# inter.net
KiCad netlist of a schematic drawn in Altium Designer
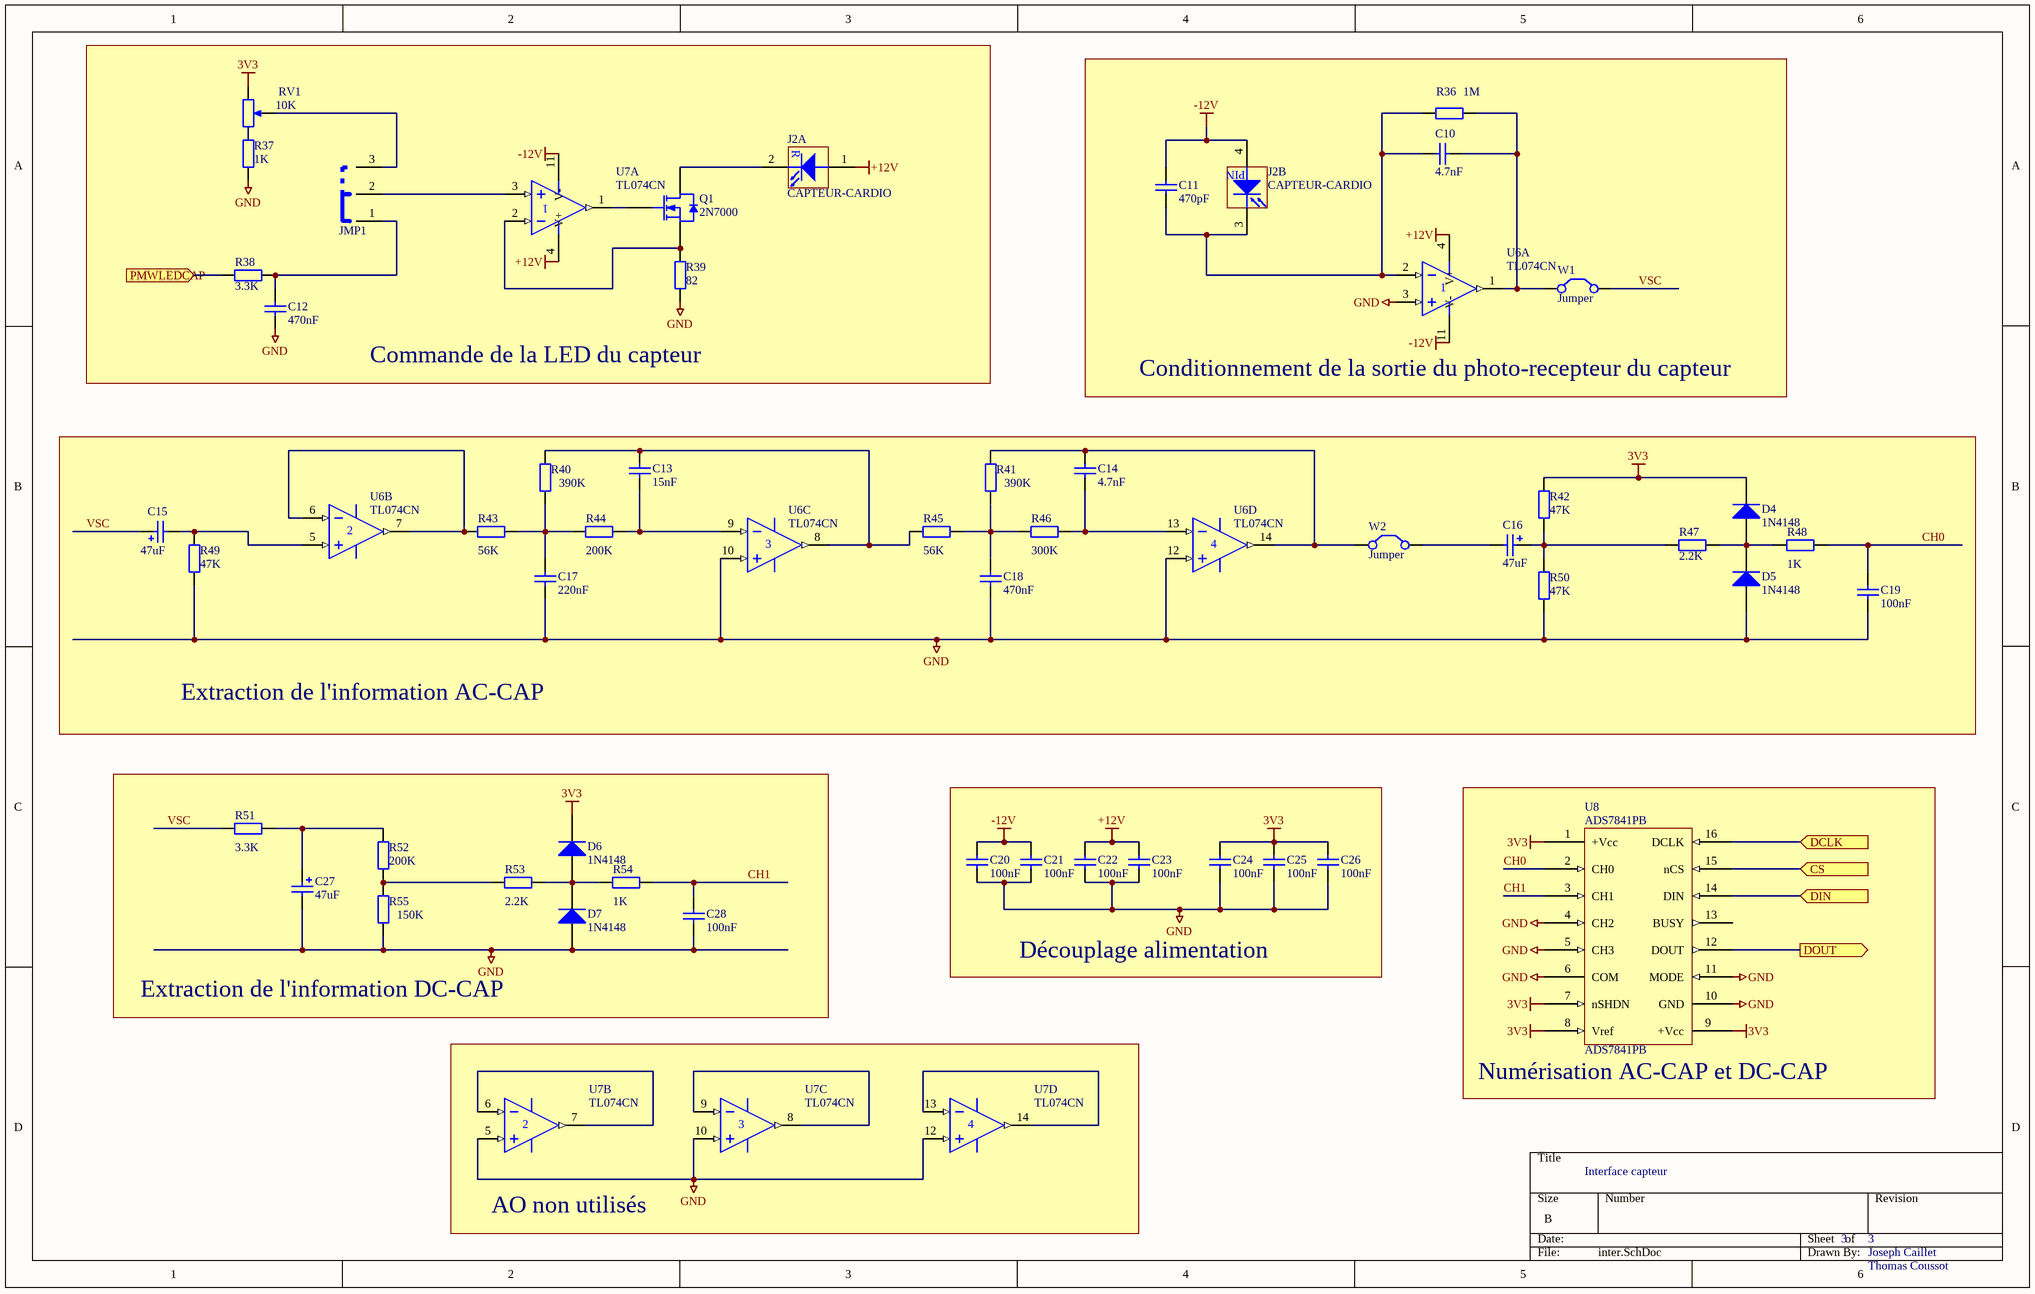
[diagram p0: inter.SchDoc]

(export (version "E")
  (design (tool "Eeschema 10.0.6"))
  (components
    (comp (ref "C10")
      (value "4.7nF")
      (footprint "rad-0.2-bot")
      (description "Capacitor Polyester 5%")
      (fields (field (name "PUBLISHER") "Altium Limited"))
      (libsource (lib "Miscellaneous Devices") (part "Cap"))
    )
    (comp (ref "C11")
      (value "470pF")
      (footprint "rad-0.2-bot")
      (description "Capacitor Polyester 5%")
      (fields (field (name "PUBLISHER") "Altium Limited"))
      (libsource (lib "Miscellaneous Devices") (part "Cap"))
    )
    (comp (ref "C12")
      (value "470nF")
      (footprint "rad-0.2-bot")
      (description "Capacitor Polyester 5%")
      (fields (field (name "PUBLISHER") "Altium Limited"))
      (libsource (lib "Miscellaneous Devices") (part "Cap"))
    )
    (comp (ref "C13")
      (value "15nF")
      (footprint "rad-0.2-bot")
      (description "Capacitor Polyester 5%")
      (fields (field (name "PUBLISHER") "Altium Limited"))
      (libsource (lib "Miscellaneous Devices") (part "Cap"))
    )
    (comp (ref "C14")
      (value "4.7nF")
      (footprint "rad-0.2-bot")
      (description "Capacitor Polyester 5%")
      (fields (field (name "PUBLISHER") "Altium Limited"))
      (libsource (lib "Miscellaneous Devices") (part "Cap"))
    )
    (comp (ref "C15")
      (value "47uF")
      (footprint "RAD-0.2-BOT")
      (description "Polarized Capacitor (Axial)")
      (fields (field (name "PUBLISHER") "Altium Limited"))
      (libsource (lib "Miscellaneous Devices") (part "Cap Pol1"))
    )
    (comp (ref "C16")
      (value "47uF")
      (footprint "RAD-0.2-BOT")
      (description "Polarized Capacitor (Axial)")
      (fields (field (name "PUBLISHER") "Altium Limited"))
      (libsource (lib "Miscellaneous Devices") (part "Cap Pol1"))
    )
    (comp (ref "C17")
      (value "220nF")
      (footprint "rad-0.2-bot")
      (description "Capacitor Polyester 5%")
      (fields (field (name "PUBLISHER") "Altium Limited"))
      (libsource (lib "Miscellaneous Devices") (part "Cap"))
    )
    (comp (ref "C18")
      (value "470nF")
      (footprint "rad-0.2-bot")
      (description "Capacitor Polyester 5%")
      (fields (field (name "PUBLISHER") "Altium Limited"))
      (libsource (lib "Miscellaneous Devices") (part "Cap"))
    )
    (comp (ref "C19")
      (value "100nF")
      (footprint "rad-0.2")
      (description "Capacitor Céramique Multicouche X7R 50V RadialPas=5.08mm 50%")
      (fields (field (name "PUBLISHER") "Altium Limited"))
      (libsource (lib "Miscellaneous Devices") (part "Cap"))
    )
    (comp (ref "C20")
      (value "100nF")
      (footprint "rad-0.2")
      (description "Capacitor Céramique Multicouche X7R 50V RadialPas=5.08mm 50%")
      (fields (field (name "PUBLISHER") "Altium Limited"))
      (libsource (lib "Miscellaneous Devices") (part "Cap"))
    )
    (comp (ref "C21")
      (value "100nF")
      (footprint "rad-0.2")
      (description "Capacitor Céramique Multicouche X7R 50V RadialPas=5.08mm 50%")
      (fields (field (name "PUBLISHER") "Altium Limited"))
      (libsource (lib "Miscellaneous Devices") (part "Cap"))
    )
    (comp (ref "C22")
      (value "100nF")
      (footprint "rad-0.2")
      (description "Capacitor Céramique Multicouche X7R 50V RadialPas=5.08mm 50%")
      (fields (field (name "PUBLISHER") "Altium Limited"))
      (libsource (lib "Miscellaneous Devices") (part "Cap"))
    )
    (comp (ref "C23")
      (value "100nF")
      (footprint "rad-0.2")
      (description "Capacitor Céramique Multicouche X7R 50V RadialPas=5.08mm 50%")
      (fields (field (name "PUBLISHER") "Altium Limited"))
      (libsource (lib "Miscellaneous Devices") (part "Cap"))
    )
    (comp (ref "C24")
      (value "100nF")
      (footprint "rad-0.2")
      (description "Capacitor Céramique Multicouche X7R 50V RadialPas=5.08mm 50%")
      (fields (field (name "PUBLISHER") "Altium Limited"))
      (libsource (lib "Miscellaneous Devices") (part "Cap"))
    )
    (comp (ref "C25")
      (value "100nF")
      (footprint "rad-0.2")
      (description "Capacitor Céramique Multicouche X7R 50V RadialPas=5.08mm 50%")
      (fields (field (name "PUBLISHER") "Altium Limited"))
      (libsource (lib "Miscellaneous Devices") (part "Cap"))
    )
    (comp (ref "C26")
      (value "100nF")
      (footprint "rad-0.2")
      (description "Capacitor Céramique Multicouche X7R 50V RadialPas=5.08mm 50%")
      (fields (field (name "PUBLISHER") "Altium Limited"))
      (libsource (lib "Miscellaneous Devices") (part "Cap"))
    )
    (comp (ref "C27")
      (value "47uF")
      (footprint "RAD-0.2-BOT")
      (description "Polarized Capacitor (Axial)")
      (fields (field (name "PUBLISHER") "Altium Limited"))
      (libsource (lib "Miscellaneous Devices") (part "Cap Pol1"))
    )
    (comp (ref "C28")
      (value "100nF")
      (footprint "rad-0.2")
      (description "Capacitor Céramique Multicouche X7R 50V RadialPas=5.08mm 50%")
      (fields (field (name "PUBLISHER") "Altium Limited"))
      (libsource (lib "Miscellaneous Devices") (part "Cap"))
    )
    (comp (ref "D4")
      (value "1N4148")
      (footprint "diode-0.4")
      (description "High Conductance Fast Diode")
      (fields (field (name "PUBLISHER") "Altium Limited"))
      (libsource (lib "FSC Discrete Diode") (part "1N4148"))
    )
    (comp (ref "D5")
      (value "1N4148")
      (footprint "diode-0.4")
      (description "High Conductance Fast Diode")
      (fields (field (name "PUBLISHER") "Altium Limited"))
      (libsource (lib "FSC Discrete Diode") (part "1N4148"))
    )
    (comp (ref "D6")
      (value "1N4148")
      (footprint "diode-0.4")
      (description "High Conductance Fast Diode")
      (fields (field (name "PUBLISHER") "Altium Limited"))
      (libsource (lib "FSC Discrete Diode") (part "1N4148"))
    )
    (comp (ref "D7")
      (value "1N4148")
      (footprint "diode-0.4")
      (description "High Conductance Fast Diode")
      (fields (field (name "PUBLISHER") "Altium Limited"))
      (libsource (lib "FSC Discrete Diode") (part "1N4148"))
    )
    (comp (ref "J2")
      (value "CAPTEUR-CARDIO")
      (footprint "KK-1X4M")
      (description "CAPTEUR CARDIO")
      (libsource (lib "schema_base_2016") (part "CAPTEUR-CARDIO"))
    )
    (comp (ref "JMP1")
      (value "JUMPER-INV")
      (footprint "JMP3-INV-0.1")
      (description "JUMPER INVERSEUR HE14 MALE 3 cts")
      (libsource (lib "schema_base_2016") (part "JUMPER-INV"))
    )
    (comp (ref "Q1")
      (value "2N7000")
      (footprint "NMOS-TO92")
      (description "N-channel Enhancement Mode Field-effect Transistor")
      (fields (field (name "PUBLISHER") "Altium Limited"))
      (libsource (lib "Philips Discrete MOSFET - Low Power") (part "2N7000"))
    )
    (comp (ref "R36")
      (value "1M")
      (footprint "axial-0.4")
      (description "Resistor 1% Couche métallique 0.4W Axial L=7mm")
      (fields (field (name "PUBLISHER") "Altium Limited"))
      (libsource (lib "") (part "Res2_3"))
    )
    (comp (ref "R37")
      (value "1K")
      (footprint "axial-0.4")
      (description "Resistor 5% Couche métallique 0.4W Axial L=7mm")
      (fields (field (name "PUBLISHER") "Altium Limited"))
      (libsource (lib "") (part "Res2_1"))
    )
    (comp (ref "R38")
      (value "3.3K")
      (footprint "axial-0.4")
      (description "Resistor 5% Couche métallique 0.4W Axial L=7mm")
      (fields (field (name "PUBLISHER") "Altium Limited"))
      (libsource (lib "") (part "Res2_3"))
    )
    (comp (ref "R39")
      (value "82")
      (footprint "axial-0.4")
      (description "Resistor 5% Couche métallique 0.4W Axial L=7mm")
      (fields (field (name "PUBLISHER") "Altium Limited"))
      (libsource (lib "") (part "Res2_2"))
    )
    (comp (ref "R40")
      (value "390K")
      (footprint "axial-0.4")
      (description "Resistor 1% Couche métallique 0.4W Axial L=7mm")
      (fields (field (name "PUBLISHER") "Altium Limited"))
      (libsource (lib "") (part "Res2_1"))
    )
    (comp (ref "R41")
      (value "390K")
      (footprint "axial-0.4")
      (description "Resistor 1% Couche métallique 0.4W Axial L=7mm")
      (fields (field (name "PUBLISHER") "Altium Limited"))
      (libsource (lib "") (part "Res2_1"))
    )
    (comp (ref "R42")
      (value "47K")
      (footprint "axial-0.4")
      (description "Resistor 1% Couche métallique 0.4W Axial L=7mm")
      (fields (field (name "PUBLISHER") "Altium Limited"))
      (libsource (lib "") (part "Res2_1"))
    )
    (comp (ref "R43")
      (value "56K")
      (footprint "axial-0.4")
      (description "Resistor 1% Couche métallique 0.4W Axial L=7mm")
      (fields (field (name "PUBLISHER") "Altium Limited"))
      (libsource (lib "Miscellaneous Devices") (part "Res2"))
    )
    (comp (ref "R44")
      (value "200K")
      (footprint "axial-0.4")
      (description "Resistor 1% Couche métallique 0.4W Axial L=7mm")
      (fields (field (name "PUBLISHER") "Altium Limited"))
      (libsource (lib "") (part "Res2_3"))
    )
    (comp (ref "R45")
      (value "56K")
      (footprint "axial-0.4")
      (description "Resistor 1% Couche métallique 0.4W Axial L=7mm")
      (fields (field (name "PUBLISHER") "Altium Limited"))
      (libsource (lib "Miscellaneous Devices") (part "Res2"))
    )
    (comp (ref "R46")
      (value "300K")
      (footprint "axial-0.4")
      (description "Resistor 1% Couche métallique 0.4W Axial L=7mm")
      (fields (field (name "PUBLISHER") "Altium Limited"))
      (libsource (lib "") (part "Res2_3"))
    )
    (comp (ref "R47")
      (value "2.2K")
      (footprint "axial-0.4")
      (description "Resistor 1% Couche métallique 0.4W Axial L=7mm")
      (fields (field (name "PUBLISHER") "Altium Limited"))
      (libsource (lib "Miscellaneous Devices") (part "Res2"))
    )
    (comp (ref "R48")
      (value "1K")
      (footprint "axial-0.4")
      (description "Resistor 5% Couche métallique 0.4W Axial L=7mm")
      (fields (field (name "PUBLISHER") "Altium Limited"))
      (libsource (lib "Miscellaneous Devices") (part "Res2"))
    )
    (comp (ref "R49")
      (value "47K")
      (footprint "axial-0.4")
      (description "Resistor 1% Couche métallique 0.4W Axial L=7mm")
      (fields (field (name "PUBLISHER") "Altium Limited"))
      (libsource (lib "") (part "Res2_1"))
    )
    (comp (ref "R50")
      (value "47K")
      (footprint "axial-0.4")
      (description "Resistor 1% Couche métallique 0.4W Axial L=7mm")
      (fields (field (name "PUBLISHER") "Altium Limited"))
      (libsource (lib "") (part "Res2_1"))
    )
    (comp (ref "R51")
      (value "3.3K")
      (footprint "axial-0.4")
      (description "Resistor 1% Couche métallique 0.4W Axial L=7mm")
      (fields (field (name "PUBLISHER") "Altium Limited"))
      (libsource (lib "Miscellaneous Devices") (part "Res2"))
    )
    (comp (ref "R52")
      (value "200K")
      (footprint "axial-0.4")
      (description "Resistor 5% Couche métallique 0.4W Axial L=7mm")
      (fields (field (name "PUBLISHER") "Altium Limited"))
      (libsource (lib "") (part "Res2_2"))
    )
    (comp (ref "R53")
      (value "2.2K")
      (footprint "axial-0.4")
      (description "Resistor 5% Couche métallique 0.4W Axial L=7mm")
      (fields (field (name "PUBLISHER") "Altium Limited"))
      (libsource (lib "Miscellaneous Devices") (part "Res2"))
    )
    (comp (ref "R54")
      (value "1K")
      (footprint "axial-0.4")
      (description "Resistor 5% Couche métallique 0.4W Axial L=7mm")
      (fields (field (name "PUBLISHER") "Altium Limited"))
      (libsource (lib "Miscellaneous Devices") (part "Res2"))
    )
    (comp (ref "R55")
      (value "150K")
      (footprint "axial-0.4")
      (description "Resistor 5% Couche métallique 0.4W Axial L=7mm")
      (fields (field (name "PUBLISHER") "Altium Limited"))
      (libsource (lib "") (part "Res2_2"))
    )
    (comp (ref "RV1")
      (value "10K")
      (footprint "VR-3386F-T")
      (description "TRIMMER PRECISION POTENTIOMETER")
      (fields (field (name "MANUFACTURER") "Bourns/Vishay"))
      (libsource (lib "schema_base_2016") (part "R-TRIM"))
    )
    (comp (ref "U6")
      (value "TL074CN")
      (footprint "dip-14")
      (description "Low-Noise JFET-Input Operational Amplifier")
      (fields (field (name "MANUFACTURER") "Texas/Motorola") (field (name "PUBLISHER") "Altium Limited"))
      (libsource (lib "") (part "TL074CN_3"))
    )
    (comp (ref "U7")
      (value "TL074CN")
      (footprint "dip-14")
      (description "Low-Noise JFET-Input Operational Amplifier")
      (fields (field (name "MANUFACTURER") "Texas/Motorola") (field (name "PUBLISHER") "Altium Limited"))
      (libsource (lib "") (part "TL074CN_2"))
    )
    (comp (ref "U8")
      (value "ADS7841PB")
      (footprint "DIP-16")
      (description "Analog to Digital converter")
      (fields (field (name "MANUFACTURER") "TEXAS"))
      (libsource (lib "ADS") (part "ADS7841PB"))
    )
    (comp (ref "W1")
      (value "Jumper")
      (footprint "JMP2-0.1")
      (description "Jumper Wire")
      (fields (field (name "PUBLISHER") "Altium Limited"))
      (libsource (lib "Miscellaneous Devices") (part "Jumper"))
    )
    (comp (ref "W2")
      (value "Jumper")
      (footprint "JMP2-0.1")
      (description "Jumper Wire")
      (fields (field (name "PUBLISHER") "Altium Limited"))
      (libsource (lib "Miscellaneous Devices") (part "Jumper"))
    )
  )
  (nets
    (net (code "1") (name "+12V") (class "Default")
      (node (ref "C22") (pin "2") (pinfunction "2_2") (pintype "passive"))
      (node (ref "C23") (pin "2") (pinfunction "2_2") (pintype "passive"))
      (node (ref "J2") (pin "1") (pinfunction "A-R_1") (pintype "passive"))
      (node (ref "U6") (pin "4") (pinfunction "V+_4") (pintype "power_in"))
      (node (ref "U7") (pin "4") (pinfunction "V+_4") (pintype "power_in"))
    )
    (net (code "2") (name "-12V") (class "Default")
      (node (ref "C11") (pin "2") (pinfunction "2_2") (pintype "passive"))
      (node (ref "C20") (pin "2") (pinfunction "2_2") (pintype "passive"))
      (node (ref "C21") (pin "2") (pinfunction "2_2") (pintype "passive"))
      (node (ref "J2") (pin "4") (pinfunction "A-DET_4") (pintype "power_in"))
      (node (ref "U6") (pin "11") (pinfunction "V-_11") (pintype "power_in"))
      (node (ref "U7") (pin "11") (pinfunction "V-_11") (pintype "power_in"))
    )
    (net (code "3") (name "/CH0") (class "Default")
      (node (ref "C19") (pin "2") (pinfunction "2_2") (pintype "passive"))
      (node (ref "R48") (pin "1") (pinfunction "1_1") (pintype "passive"))
      (node (ref "U8") (pin "2") (pinfunction "CH0_2") (pintype "input"))
    )
    (net (code "4") (name "/CH1") (class "Default")
      (node (ref "C28") (pin "2") (pinfunction "2_2") (pintype "passive"))
      (node (ref "R54") (pin "1") (pinfunction "1_1") (pintype "passive"))
      (node (ref "U8") (pin "3") (pinfunction "CH1_3") (pintype "input"))
    )
    (net (code "5") (name "/CS") (class "Default")
      (node (ref "U8") (pin "15") (pinfunction "nCS_15") (pintype "input"))
    )
    (net (code "6") (name "/DCLK") (class "Default")
      (node (ref "U8") (pin "16") (pinfunction "DCLK_16") (pintype "input"))
    )
    (net (code "7") (name "/DIN") (class "Default")
      (node (ref "U8") (pin "14") (pinfunction "DIN_14") (pintype "input"))
    )
    (net (code "8") (name "/DOUT") (class "Default")
      (node (ref "U8") (pin "12") (pinfunction "DOUT_12") (pintype "output"))
    )
    (net (code "9") (name "/PMWLEDCAP") (class "Default")
      (node (ref "R38") (pin "1") (pinfunction "1_1") (pintype "passive"))
    )
    (net (code "10") (name "/VSC") (class "Default")
      (node (ref "C15") (pin "1") (pinfunction "1_1") (pintype "passive"))
      (node (ref "R51") (pin "2") (pinfunction "2_2") (pintype "passive"))
      (node (ref "W1") (pin "2") (pinfunction "C2_2") (pintype "passive"))
    )
    (net (code "11") (name "3V3") (class "Default")
      (node (ref "C24") (pin "2") (pinfunction "2_2") (pintype "passive"))
      (node (ref "C25") (pin "2") (pinfunction "2_2") (pintype "passive"))
      (node (ref "C26") (pin "2") (pinfunction "2_2") (pintype "passive"))
      (node (ref "D4") (pin "2") (pinfunction "K_2") (pintype "passive"))
      (node (ref "D6") (pin "2") (pinfunction "K_2") (pintype "passive"))
      (node (ref "R42") (pin "2") (pinfunction "2_2") (pintype "passive"))
      (node (ref "RV1") (pin "2") (pinfunction "BOT_2") (pintype "passive"))
      (node (ref "U8") (pin "1") (pinfunction "+Vcc_1") (pintype "power_in"))
      (node (ref "U8") (pin "7") (pinfunction "nSHDN_7") (pintype "input"))
      (node (ref "U8") (pin "8") (pinfunction "Vref_8") (pintype "input"))
      (node (ref "U8") (pin "9") (pinfunction "+Vcc_9") (pintype "power_in"))
    )
    (net (code "12") (name "GND") (class "Default")
      (node (ref "C12") (pin "1") (pinfunction "1_1") (pintype "passive"))
      (node (ref "C17") (pin "2") (pinfunction "2_2") (pintype "passive"))
      (node (ref "C18") (pin "2") (pinfunction "2_2") (pintype "passive"))
      (node (ref "C19") (pin "1") (pinfunction "1_1") (pintype "passive"))
      (node (ref "C20") (pin "1") (pinfunction "1_1") (pintype "passive"))
      (node (ref "C21") (pin "1") (pinfunction "1_1") (pintype "passive"))
      (node (ref "C22") (pin "1") (pinfunction "1_1") (pintype "passive"))
      (node (ref "C23") (pin "1") (pinfunction "1_1") (pintype "passive"))
      (node (ref "C24") (pin "1") (pinfunction "1_1") (pintype "passive"))
      (node (ref "C25") (pin "1") (pinfunction "1_1") (pintype "passive"))
      (node (ref "C26") (pin "1") (pinfunction "1_1") (pintype "passive"))
      (node (ref "C27") (pin "2") (pinfunction "2_2") (pintype "passive"))
      (node (ref "C28") (pin "1") (pinfunction "1_1") (pintype "passive"))
      (node (ref "D5") (pin "1") (pinfunction "A_1") (pintype "passive"))
      (node (ref "D7") (pin "1") (pinfunction "A_1") (pintype "passive"))
      (node (ref "R37") (pin "1") (pinfunction "1_1") (pintype "passive"))
      (node (ref "R39") (pin "2") (pinfunction "2_2") (pintype "passive"))
      (node (ref "R49") (pin "1") (pinfunction "1_1") (pintype "passive"))
      (node (ref "R50") (pin "1") (pinfunction "1_1") (pintype "passive"))
      (node (ref "R55") (pin "2") (pinfunction "2_2") (pintype "passive"))
      (node (ref "U6") (pin "10") (pinfunction "IN+_10") (pintype "input"))
      (node (ref "U6") (pin "12") (pinfunction "IN+_12") (pintype "input"))
      (node (ref "U6") (pin "3") (pinfunction "IN+_3") (pintype "input"))
      (node (ref "U7") (pin "10") (pinfunction "IN+_10") (pintype "input"))
      (node (ref "U7") (pin "12") (pinfunction "IN+_12") (pintype "input"))
      (node (ref "U7") (pin "5") (pinfunction "IN+_5") (pintype "input"))
      (node (ref "U8") (pin "10") (pinfunction "GND_10") (pintype "power_in"))
      (node (ref "U8") (pin "11") (pinfunction "MODE_11") (pintype "input"))
      (node (ref "U8") (pin "4") (pinfunction "CH2_4") (pintype "input"))
      (node (ref "U8") (pin "5") (pinfunction "CH3_5") (pintype "input"))
      (node (ref "U8") (pin "6") (pinfunction "COM_6") (pintype "power_in"))
    )
    (net (code "13") (name "Net-(C12-Pad2)") (class "Default")
      (node (ref "C12") (pin "2") (pinfunction "2_2") (pintype "passive"))
      (node (ref "JMP1") (pin "1") (pintype "passive"))
      (node (ref "R38") (pin "2") (pinfunction "2_2") (pintype "passive"))
    )
    (net (code "14") (name "Net-(C16-Pad1)") (class "Default")
      (node (ref "C16") (pin "1") (pinfunction "1_1") (pintype "passive"))
      (node (ref "R42") (pin "1") (pinfunction "1_1") (pintype "passive"))
      (node (ref "R47") (pin "2") (pinfunction "2_2") (pintype "passive"))
      (node (ref "R50") (pin "2") (pinfunction "2_2") (pintype "passive"))
    )
    (net (code "15") (name "Net-(C17-Pad1)") (class "Default")
      (node (ref "C17") (pin "1") (pinfunction "1_1") (pintype "passive"))
      (node (ref "R40") (pin "1") (pinfunction "1_1") (pintype "passive"))
      (node (ref "R43") (pin "1") (pinfunction "1_1") (pintype "passive"))
      (node (ref "R44") (pin "1") (pinfunction "1_1") (pintype "passive"))
    )
    (net (code "16") (name "Net-(C18-Pad1)") (class "Default")
      (node (ref "C18") (pin "1") (pinfunction "1_1") (pintype "passive"))
      (node (ref "R41") (pin "1") (pinfunction "1_1") (pintype "passive"))
      (node (ref "R45") (pin "1") (pinfunction "1_1") (pintype "passive"))
      (node (ref "R46") (pin "1") (pinfunction "1_1") (pintype "passive"))
    )
    (net (code "17") (name "Net-(C27-Pad1)") (class "Default")
      (node (ref "C27") (pin "1") (pinfunction "1_1") (pintype "passive"))
      (node (ref "R51") (pin "1") (pinfunction "1_1") (pintype "passive"))
      (node (ref "R52") (pin "1") (pinfunction "1_1") (pintype "passive"))
    )
    (net (code "18") (name "Net-(D4-A)") (class "Default")
      (node (ref "D4") (pin "1") (pinfunction "A_1") (pintype "passive"))
      (node (ref "D5") (pin "2") (pinfunction "K_2") (pintype "passive"))
      (node (ref "R47") (pin "1") (pinfunction "1_1") (pintype "passive"))
      (node (ref "R48") (pin "2") (pinfunction "2_2") (pintype "passive"))
    )
    (net (code "19") (name "Net-(D6-A)") (class "Default")
      (node (ref "D6") (pin "1") (pinfunction "A_1") (pintype "passive"))
      (node (ref "D7") (pin "2") (pinfunction "K_2") (pintype "passive"))
      (node (ref "R53") (pin "1") (pinfunction "1_1") (pintype "passive"))
      (node (ref "R54") (pin "2") (pinfunction "2_2") (pintype "passive"))
    )
    (net (code "20") (name "Net-(J2A-K-R)") (class "Default")
      (node (ref "J2") (pin "2") (pinfunction "K-R_2") (pintype "passive"))
      (node (ref "Q1") (pin "1") (pinfunction "D_1") (pintype "passive"))
    )
    (net (code "21") (name "Net-(J2B-K-DET)") (class "Default")
      (node (ref "C10") (pin "2") (pinfunction "2_2") (pintype "passive"))
      (node (ref "C11") (pin "1") (pinfunction "1_1") (pintype "passive"))
      (node (ref "J2") (pin "3") (pinfunction "K-DET_3") (pintype "passive"))
      (node (ref "R36") (pin "1") (pinfunction "1_1") (pintype "passive"))
      (node (ref "U6") (pin "2") (pinfunction "IN-_2") (pintype "input"))
    )
    (net (code "22") (name "Net-(Q1-G)") (class "Default")
      (node (ref "Q1") (pin "2") (pinfunction "G_2") (pintype "passive"))
      (node (ref "U7") (pin "1") (pinfunction "OUT_1") (pintype "output"))
    )
    (net (code "23") (name "Net-(Q1-S)") (class "Default")
      (node (ref "Q1") (pin "3") (pinfunction "S_3") (pintype "passive"))
      (node (ref "R39") (pin "1") (pinfunction "1_1") (pintype "passive"))
      (node (ref "U7") (pin "2") (pinfunction "IN-_2") (pintype "input"))
    )
    (net (code "24") (name "Net-(R52-Pad2)") (class "Default")
      (node (ref "R52") (pin "2") (pinfunction "2_2") (pintype "passive"))
      (node (ref "R53") (pin "2") (pinfunction "2_2") (pintype "passive"))
      (node (ref "R55") (pin "1") (pinfunction "1_1") (pintype "passive"))
    )
    (net (code "25") (name "Net-(RV1-TAP)") (class "Default")
      (node (ref "JMP1") (pin "3") (pintype "passive"))
      (node (ref "RV1") (pin "3") (pinfunction "TAP_3") (pintype "passive"))
    )
    (net (code "26") (name "Net-(RV1-TOP)") (class "Default")
      (node (ref "R37") (pin "2") (pinfunction "2_2") (pintype "passive"))
      (node (ref "RV1") (pin "1") (pinfunction "TOP_1") (pintype "passive"))
    )
    (net (code "27") (name "Net-(U6A-OUT)") (class "Default")
      (node (ref "C10") (pin "1") (pinfunction "1_1") (pintype "passive"))
      (node (ref "R36") (pin "2") (pinfunction "2_2") (pintype "passive"))
      (node (ref "U6") (pin "1") (pinfunction "OUT_1") (pintype "output"))
      (node (ref "W1") (pin "1") (pinfunction "C1_1") (pintype "passive"))
    )
    (net (code "28") (name "Net-(U6B-IN+)") (class "Default")
      (node (ref "C15") (pin "2") (pinfunction "2_2") (pintype "passive"))
      (node (ref "R49") (pin "2") (pinfunction "2_2") (pintype "passive"))
      (node (ref "U6") (pin "5") (pinfunction "IN+_5") (pintype "input"))
    )
    (net (code "29") (name "Net-(U6B-IN-)") (class "Default")
      (node (ref "R43") (pin "2") (pinfunction "2_2") (pintype "passive"))
      (node (ref "U6") (pin "6") (pinfunction "IN-_6") (pintype "input"))
      (node (ref "U6") (pin "7") (pinfunction "OUT_7") (pintype "output"))
    )
    (net (code "30") (name "Net-(U6C-IN-)") (class "Default")
      (node (ref "C13") (pin "2") (pinfunction "2_2") (pintype "passive"))
      (node (ref "R44") (pin "2") (pinfunction "2_2") (pintype "passive"))
      (node (ref "U6") (pin "9") (pinfunction "IN-_9") (pintype "input"))
    )
    (net (code "31") (name "Net-(U6C-OUT)") (class "Default")
      (node (ref "C13") (pin "1") (pinfunction "1_1") (pintype "passive"))
      (node (ref "R40") (pin "2") (pinfunction "2_2") (pintype "passive"))
      (node (ref "R45") (pin "2") (pinfunction "2_2") (pintype "passive"))
      (node (ref "U6") (pin "8") (pinfunction "OUT_8") (pintype "output"))
    )
    (net (code "32") (name "Net-(U6D-IN-)") (class "Default")
      (node (ref "C14") (pin "2") (pinfunction "2_2") (pintype "passive"))
      (node (ref "R46") (pin "2") (pinfunction "2_2") (pintype "passive"))
      (node (ref "U6") (pin "13") (pinfunction "IN-_13") (pintype "input"))
    )
    (net (code "33") (name "Net-(U6D-OUT)") (class "Default")
      (node (ref "C14") (pin "1") (pinfunction "1_1") (pintype "passive"))
      (node (ref "R41") (pin "2") (pinfunction "2_2") (pintype "passive"))
      (node (ref "U6") (pin "14") (pinfunction "OUT_14") (pintype "output"))
      (node (ref "W2") (pin "1") (pinfunction "C1_1") (pintype "passive"))
    )
    (net (code "34") (name "Net-(U7A-IN+)") (class "Default")
      (node (ref "JMP1") (pin "2") (pintype "passive"))
      (node (ref "U7") (pin "3") (pinfunction "IN+_3") (pintype "input"))
    )
    (net (code "35") (name "Net-(U7B-IN-)") (class "Default")
      (node (ref "U7") (pin "6") (pinfunction "IN-_6") (pintype "input"))
      (node (ref "U7") (pin "7") (pinfunction "OUT_7") (pintype "output"))
    )
    (net (code "36") (name "Net-(U7C-IN-)") (class "Default")
      (node (ref "U7") (pin "8") (pinfunction "OUT_8") (pintype "output"))
      (node (ref "U7") (pin "9") (pinfunction "IN-_9") (pintype "input"))
    )
    (net (code "37") (name "Net-(U7D-IN-)") (class "Default")
      (node (ref "U7") (pin "13") (pinfunction "IN-_13") (pintype "input"))
      (node (ref "U7") (pin "14") (pinfunction "OUT_14") (pintype "output"))
    )
    (net (code "38") (name "Net-(W2-C2)") (class "Default")
      (node (ref "C16") (pin "2") (pinfunction "2_2") (pintype "passive"))
      (node (ref "W2") (pin "2") (pinfunction "C2_2") (pintype "passive"))
    )
    (net (code "39") (name "unconnected-(U8-BUSY-Pad13)") (class "Default")
      (node (ref "U8") (pin "13") (pinfunction "BUSY_13") (pintype "output"))
    )
  )
)
